# minimal_terminalv2_rc2014.net
KiCad netlist of a schematic drawn in EAGLE
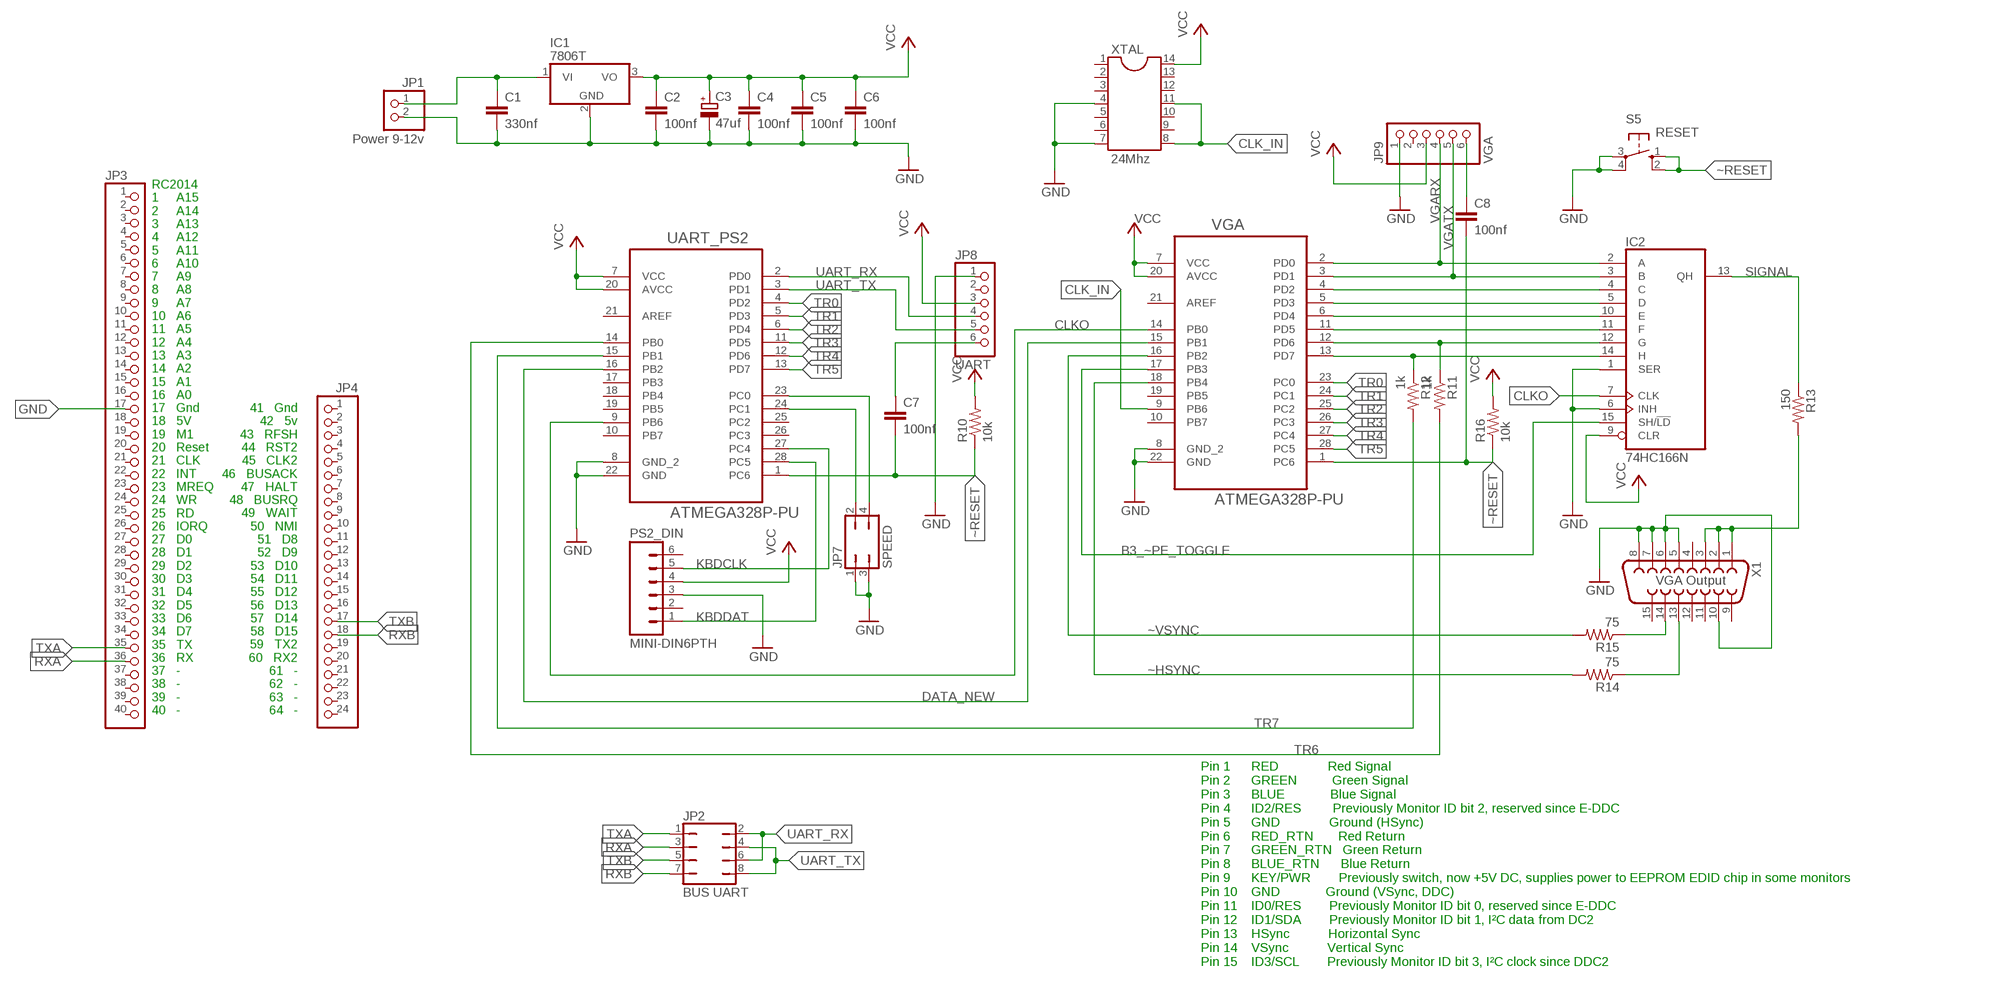
[diagram p0: schematic, sheet 1]

(export (version "E")
  (design (tool "Eeschema 10.0.6"))
  (components
    (comp (ref "C1")
      (value "330nf")
      (footprint "eagle-import:C2.5-3")
      (libsource (lib "eagle-import") (part "C2,5-3"))
    )
    (comp (ref "C2")
      (value "100nf")
      (footprint "eagle-import:C2.5-3")
      (libsource (lib "eagle-import") (part "C2,5-3"))
    )
    (comp (ref "C3")
      (value "47uf")
      (footprint "eagle-import:E2,5-6")
      (libsource (lib "eagle-import") (part "CPOL-EUE2.5-6"))
    )
    (comp (ref "C4")
      (value "100nf")
      (footprint "eagle-import:C2.5-3")
      (libsource (lib "eagle-import") (part "C2,5-3"))
    )
    (comp (ref "C5")
      (value "100nf")
      (footprint "eagle-import:C2.5-3")
      (libsource (lib "eagle-import") (part "C2,5-3"))
    )
    (comp (ref "C6")
      (value "100nf")
      (footprint "eagle-import:C2.5-3")
      (libsource (lib "eagle-import") (part "C2,5-3"))
    )
    (comp (ref "C7")
      (value "100nf")
      (footprint "eagle-import:C2.5-3")
      (libsource (lib "eagle-import") (part "C2,5-3"))
    )
    (comp (ref "C8")
      (value "100nf")
      (footprint "eagle-import:C2.5-3")
      (libsource (lib "eagle-import") (part "C2,5-3"))
    )
    (comp (ref "IC1")
      (value "7806T")
      (footprint "eagle-import:TO220H")
      (libsource (lib "eagle-import") (part "78T06"))
    )
    (comp (ref "IC2")
      (value "74HC166N")
      (footprint "eagle-import:DIL16")
      (libsource (lib "eagle-import") (part "74166NHC"))
    )
    (comp (ref "JP1")
      (value "Power 9-12v")
      (footprint "eagle-import:1X02")
      (libsource (lib "eagle-import") (part "PINHD-1X2"))
    )
    (comp (ref "JP2")
      (value "BUS UART")
      (footprint "eagle-import:JP4Q")
      (libsource (lib "eagle-import") (part "JP4Q"))
    )
    (comp (ref "JP3")
      (value "PINHD-1X40")
      (footprint "eagle-import:1X40")
      (libsource (lib "eagle-import") (part "PINHD-1X40"))
    )
    (comp (ref "JP4")
      (value "PINHD-1X24")
      (footprint "eagle-import:1X24")
      (libsource (lib "eagle-import") (part "PINHD-1X24"))
    )
    (comp (ref "JP7")
      (value "SPEED")
      (footprint "eagle-import:JP2Q")
      (libsource (lib "eagle-import") (part "JP2Q"))
    )
    (comp (ref "JP8")
      (value "UART")
      (footprint "eagle-import:1X06")
      (libsource (lib "eagle-import") (part "PINHD-1X6"))
    )
    (comp (ref "JP9")
      (value "VGA")
      (footprint "eagle-import:1X06")
      (libsource (lib "eagle-import") (part "PINHD-1X6"))
    )
    (comp (ref "PS2_DIN")
      (value "MINI-DIN6PTH")
      (footprint "eagle-import:MINI-DIN6")
      (libsource (lib "eagle-import") (part "MINI-DIN6PTH"))
    )
    (comp (ref "R10")
      (value "10k")
      (footprint "eagle-import:0204_7")
      (libsource (lib "eagle-import") (part "R-US_0204/7"))
    )
    (comp (ref "R11")
      (value "1k")
      (footprint "eagle-import:0204_7")
      (libsource (lib "eagle-import") (part "R-US_0204/7"))
    )
    (comp (ref "R12")
      (value "1k")
      (footprint "eagle-import:0204_7")
      (libsource (lib "eagle-import") (part "R-US_0204/7"))
    )
    (comp (ref "R13")
      (value "150")
      (footprint "eagle-import:0204_7")
      (libsource (lib "eagle-import") (part "R-US_0204/7"))
    )
    (comp (ref "R14")
      (value "75")
      (footprint "eagle-import:0204_7")
      (libsource (lib "eagle-import") (part "R-US_0204/7"))
    )
    (comp (ref "R15")
      (value "75")
      (footprint "eagle-import:0204_7")
      (libsource (lib "eagle-import") (part "R-US_0204/7"))
    )
    (comp (ref "R16")
      (value "10k")
      (footprint "eagle-import:0204_7")
      (libsource (lib "eagle-import") (part "R-US_0204/7"))
    )
    (comp (ref "S5")
      (value "RESET")
      (footprint "eagle-import:B3F-10XX")
      (fields (field (name "MPN") "B3F-1000"))
      (libsource (lib "eagle-import") (part "10-XX"))
    )
    (comp (ref "UART_PS2")
      (value "ATMEGA328P-PU")
      (footprint "eagle-import:DIP254P762X457-28")
      (libsource (lib "eagle-import") (part "ATMEGA328P-PU"))
    )
    (comp (ref "VGA")
      (value "ATMEGA328P-PU")
      (footprint "eagle-import:DIP254P762X457-28")
      (libsource (lib "eagle-import") (part "ATMEGA328P-PU"))
    )
    (comp (ref "X1")
      (value "VGA Output")
      (footprint "eagle-import:HDF15H")
      (libsource (lib "eagle-import") (part "F15HDH"))
    )
    (comp (ref "XTAL")
      (value "24Mhz")
      (footprint "eagle-import:SOCKET-14")
      (libsource (lib "eagle-import") (part "DIL14S"))
    )
  )
  (nets
    (net (code "1") (name "/B3_~{PE_TOGGLE}") (class "Default")
      (node (ref "IC2") (pin "15") (pinfunction "SH/~{LD}_15") (pintype "input"))
      (node (ref "VGA") (pin "17") (pinfunction "PB3_17") (pintype "bidirectional"))
    )
    (net (code "2") (name "/DATA_NEW") (class "Default")
      (node (ref "UART_PS2") (pin "16") (pinfunction "PB2_16") (pintype "bidirectional"))
      (node (ref "VGA") (pin "15") (pinfunction "PB1_15") (pintype "bidirectional"))
    )
    (net (code "3") (name "/KBDCLK") (class "Default")
      (node (ref "PS2_DIN") (pin "5") (pinfunction "5_5") (pintype "passive"))
      (node (ref "UART_PS2") (pin "27") (pinfunction "PC4_27") (pintype "bidirectional"))
    )
    (net (code "4") (name "/KBDDAT") (class "Default")
      (node (ref "PS2_DIN") (pin "1") (pinfunction "1_1") (pintype "passive"))
      (node (ref "UART_PS2") (pin "28") (pinfunction "PC5_28") (pintype "bidirectional"))
    )
    (net (code "5") (name "/SIGNAL") (class "Default")
      (node (ref "IC2") (pin "13") (pinfunction "QH_13") (pintype "output"))
      (node (ref "R13") (pin "1") (pinfunction "1_1") (pintype "passive"))
    )
    (net (code "6") (name "/TR6") (class "Default")
      (node (ref "R11") (pin "2") (pinfunction "2_2") (pintype "passive"))
      (node (ref "UART_PS2") (pin "14") (pinfunction "PB0_14") (pintype "bidirectional"))
    )
    (net (code "7") (name "/TR7") (class "Default")
      (node (ref "R12") (pin "2") (pinfunction "2_2") (pintype "passive"))
      (node (ref "UART_PS2") (pin "15") (pinfunction "PB1_15") (pintype "bidirectional"))
    )
    (net (code "8") (name "/VGARX") (class "Default")
      (node (ref "IC2") (pin "2") (pinfunction "A_2") (pintype "input"))
      (node (ref "JP9") (pin "4") (pinfunction "4_4") (pintype "passive"))
      (node (ref "VGA") (pin "2") (pinfunction "PD0_2") (pintype "bidirectional"))
    )
    (net (code "9") (name "/VGATX") (class "Default")
      (node (ref "IC2") (pin "3") (pinfunction "B_3") (pintype "input"))
      (node (ref "JP9") (pin "5") (pinfunction "5_5") (pintype "passive"))
      (node (ref "VGA") (pin "3") (pinfunction "PD1_3") (pintype "bidirectional"))
    )
    (net (code "10") (name "/~{HSYNC}") (class "Default")
      (node (ref "R14") (pin "2") (pinfunction "2_2") (pintype "passive"))
      (node (ref "VGA") (pin "18") (pinfunction "PB4_18") (pintype "bidirectional"))
    )
    (net (code "11") (name "/~{RESET}") (class "Default")
      (node (ref "C7") (pin "2") (pinfunction "2_2") (pintype "passive"))
      (node (ref "C8") (pin "2") (pinfunction "2_2") (pintype "passive"))
      (node (ref "R10") (pin "1") (pinfunction "1_1") (pintype "passive"))
      (node (ref "R16") (pin "1") (pinfunction "1_1") (pintype "passive"))
      (node (ref "S5") (pin "1") (pinfunction "S_1") (pintype "passive"))
      (node (ref "S5") (pin "2") (pinfunction "S1_2") (pintype "passive"))
      (node (ref "UART_PS2") (pin "1") (pinfunction "PC6_1") (pintype "bidirectional"))
      (node (ref "VGA") (pin "1") (pinfunction "PC6_1") (pintype "bidirectional"))
    )
    (net (code "12") (name "/~{VSYNC}") (class "Default")
      (node (ref "R15") (pin "2") (pinfunction "2_2") (pintype "passive"))
      (node (ref "VGA") (pin "16") (pinfunction "PB2_16") (pintype "bidirectional"))
    )
    (net (code "13") (name "CLKO") (class "Default")
      (node (ref "IC2") (pin "7") (pinfunction "CLK_7") (pintype "input"))
      (node (ref "UART_PS2") (pin "9") (pinfunction "PB6_9") (pintype "bidirectional"))
      (node (ref "VGA") (pin "14") (pinfunction "PB0_14") (pintype "bidirectional"))
    )
    (net (code "14") (name "CLK_IN") (class "Default")
      (node (ref "VGA") (pin "9") (pinfunction "PB6_9") (pintype "bidirectional"))
      (node (ref "XTAL") (pin "11") (pinfunction "11_11") (pintype "passive"))
      (node (ref "XTAL") (pin "8") (pinfunction "8_8") (pintype "passive"))
    )
    (net (code "15") (name "GND") (class "Default")
      (node (ref "C1") (pin "2") (pinfunction "2_2") (pintype "passive"))
      (node (ref "C2") (pin "2") (pinfunction "2_2") (pintype "passive"))
      (node (ref "C3") (pin "-") (pinfunction "-_-") (pintype "passive"))
      (node (ref "C4") (pin "2") (pinfunction "2_2") (pintype "passive"))
      (node (ref "C5") (pin "2") (pinfunction "2_2") (pintype "passive"))
      (node (ref "C6") (pin "2") (pinfunction "2_2") (pintype "passive"))
      (node (ref "IC1") (pin "2") (pinfunction "GND_2") (pintype "passive"))
      (node (ref "IC2") (pin "1") (pinfunction "SER_1") (pintype "input"))
      (node (ref "IC2") (pin "6") (pinfunction "INH_6") (pintype "input"))
      (node (ref "JP1") (pin "2") (pinfunction "2_2") (pintype "passive"))
      (node (ref "JP3") (pin "17") (pinfunction "17_17") (pintype "passive"))
      (node (ref "JP7") (pin "1") (pinfunction "1_1") (pintype "passive"))
      (node (ref "JP7") (pin "3") (pinfunction "3_3") (pintype "passive"))
      (node (ref "JP8") (pin "1") (pinfunction "1_1") (pintype "passive"))
      (node (ref "JP9") (pin "1") (pinfunction "1_1") (pintype "passive"))
      (node (ref "PS2_DIN") (pin "3") (pinfunction "3_3") (pintype "passive"))
      (node (ref "S5") (pin "3") (pinfunction "P_3") (pintype "passive"))
      (node (ref "S5") (pin "4") (pinfunction "P1_4") (pintype "passive"))
      (node (ref "UART_PS2") (pin "22") (pinfunction "GND_22") (pintype "passive"))
      (node (ref "UART_PS2") (pin "8") (pinfunction "GND_2_8") (pintype "passive"))
      (node (ref "VGA") (pin "22") (pinfunction "GND_22") (pintype "passive"))
      (node (ref "VGA") (pin "8") (pinfunction "GND_2_8") (pintype "passive"))
      (node (ref "X1") (pin "10") (pinfunction "10_10") (pintype "passive"))
      (node (ref "X1") (pin "5") (pinfunction "5_5") (pintype "passive"))
      (node (ref "X1") (pin "6") (pinfunction "6_6") (pintype "passive"))
      (node (ref "X1") (pin "7") (pinfunction "7_7") (pintype "passive"))
      (node (ref "X1") (pin "8") (pinfunction "8_8") (pintype "passive"))
      (node (ref "XTAL") (pin "4") (pinfunction "4_4") (pintype "passive"))
      (node (ref "XTAL") (pin "7") (pinfunction "7_7") (pintype "passive"))
    )
    (net (code "16") (name "Net-(C7-Pad1)") (class "Default")
      (node (ref "C7") (pin "1") (pinfunction "1_1") (pintype "passive"))
      (node (ref "JP8") (pin "6") (pinfunction "6_6") (pintype "passive"))
    )
    (net (code "17") (name "Net-(C8-Pad1)") (class "Default")
      (node (ref "C8") (pin "1") (pinfunction "1_1") (pintype "passive"))
      (node (ref "JP9") (pin "6") (pinfunction "6_6") (pintype "passive"))
    )
    (net (code "18") (name "Net-(IC1-VI)") (class "Default")
      (node (ref "C1") (pin "1") (pinfunction "1_1") (pintype "passive"))
      (node (ref "IC1") (pin "1") (pinfunction "VI_1") (pintype "input"))
      (node (ref "JP1") (pin "1") (pinfunction "1_1") (pintype "passive"))
    )
    (net (code "19") (name "Net-(IC2A-C)") (class "Default")
      (node (ref "IC2") (pin "4") (pinfunction "C_4") (pintype "input"))
      (node (ref "VGA") (pin "4") (pinfunction "PD2_4") (pintype "bidirectional"))
    )
    (net (code "20") (name "Net-(IC2A-D)") (class "Default")
      (node (ref "IC2") (pin "5") (pinfunction "D_5") (pintype "input"))
      (node (ref "VGA") (pin "5") (pinfunction "PD3_5") (pintype "bidirectional"))
    )
    (net (code "21") (name "Net-(IC2A-E)") (class "Default")
      (node (ref "IC2") (pin "10") (pinfunction "E_10") (pintype "input"))
      (node (ref "VGA") (pin "6") (pinfunction "PD4_6") (pintype "bidirectional"))
    )
    (net (code "22") (name "Net-(IC2A-F)") (class "Default")
      (node (ref "IC2") (pin "11") (pinfunction "F_11") (pintype "input"))
      (node (ref "VGA") (pin "11") (pinfunction "PD5_11") (pintype "bidirectional"))
    )
    (net (code "23") (name "Net-(IC2A-G)") (class "Default")
      (node (ref "IC2") (pin "12") (pinfunction "G_12") (pintype "input"))
      (node (ref "R11") (pin "1") (pinfunction "1_1") (pintype "passive"))
      (node (ref "VGA") (pin "12") (pinfunction "PD6_12") (pintype "bidirectional"))
    )
    (net (code "24") (name "Net-(IC2A-H)") (class "Default")
      (node (ref "IC2") (pin "14") (pinfunction "H_14") (pintype "input"))
      (node (ref "R12") (pin "1") (pinfunction "1_1") (pintype "passive"))
      (node (ref "VGA") (pin "13") (pinfunction "PD7_13") (pintype "bidirectional"))
    )
    (net (code "25") (name "Net-(R13-Pad2)") (class "Default")
      (node (ref "R13") (pin "2") (pinfunction "2_2") (pintype "passive"))
      (node (ref "X1") (pin "1") (pinfunction "1_1") (pintype "passive"))
      (node (ref "X1") (pin "2") (pinfunction "2_2") (pintype "passive"))
      (node (ref "X1") (pin "3") (pinfunction "3_3") (pintype "passive"))
    )
    (net (code "26") (name "Net-(R14-Pad1)") (class "Default")
      (node (ref "R14") (pin "1") (pinfunction "1_1") (pintype "passive"))
      (node (ref "X1") (pin "13") (pinfunction "13_13") (pintype "passive"))
    )
    (net (code "27") (name "Net-(R15-Pad1)") (class "Default")
      (node (ref "R15") (pin "1") (pinfunction "1_1") (pintype "passive"))
      (node (ref "X1") (pin "14") (pinfunction "14_14") (pintype "passive"))
    )
    (net (code "28") (name "Net-(UART_PS2-PC0)") (class "Default")
      (node (ref "JP7") (pin "4") (pinfunction "4_4") (pintype "passive"))
      (node (ref "UART_PS2") (pin "23") (pinfunction "PC0_23") (pintype "bidirectional"))
    )
    (net (code "29") (name "Net-(UART_PS2-PC1)") (class "Default")
      (node (ref "JP7") (pin "2") (pinfunction "2_2") (pintype "passive"))
      (node (ref "UART_PS2") (pin "24") (pinfunction "PC1_24") (pintype "bidirectional"))
    )
    (net (code "30") (name "RXA") (class "Default")
      (node (ref "JP2") (pin "3") (pinfunction "3_3") (pintype "passive"))
      (node (ref "JP3") (pin "36") (pinfunction "36_36") (pintype "passive"))
    )
    (net (code "31") (name "RXB") (class "Default")
      (node (ref "JP2") (pin "7") (pinfunction "7_7") (pintype "passive"))
      (node (ref "JP4") (pin "18") (pinfunction "18_18") (pintype "passive"))
    )
    (net (code "32") (name "TR0") (class "Default")
      (node (ref "UART_PS2") (pin "4") (pinfunction "PD2_4") (pintype "bidirectional"))
      (node (ref "VGA") (pin "23") (pinfunction "PC0_23") (pintype "bidirectional"))
    )
    (net (code "33") (name "TR1") (class "Default")
      (node (ref "UART_PS2") (pin "5") (pinfunction "PD3_5") (pintype "bidirectional"))
      (node (ref "VGA") (pin "24") (pinfunction "PC1_24") (pintype "bidirectional"))
    )
    (net (code "34") (name "TR2") (class "Default")
      (node (ref "UART_PS2") (pin "6") (pinfunction "PD4_6") (pintype "bidirectional"))
      (node (ref "VGA") (pin "25") (pinfunction "PC2_25") (pintype "bidirectional"))
    )
    (net (code "35") (name "TR3") (class "Default")
      (node (ref "UART_PS2") (pin "11") (pinfunction "PD5_11") (pintype "bidirectional"))
      (node (ref "VGA") (pin "26") (pinfunction "PC3_26") (pintype "bidirectional"))
    )
    (net (code "36") (name "TR4") (class "Default")
      (node (ref "UART_PS2") (pin "12") (pinfunction "PD6_12") (pintype "bidirectional"))
      (node (ref "VGA") (pin "27") (pinfunction "PC4_27") (pintype "bidirectional"))
    )
    (net (code "37") (name "TR5") (class "Default")
      (node (ref "UART_PS2") (pin "13") (pinfunction "PD7_13") (pintype "bidirectional"))
      (node (ref "VGA") (pin "28") (pinfunction "PC5_28") (pintype "bidirectional"))
    )
    (net (code "38") (name "TXA") (class "Default")
      (node (ref "JP2") (pin "1") (pinfunction "1_1") (pintype "passive"))
      (node (ref "JP3") (pin "35") (pinfunction "35_35") (pintype "passive"))
    )
    (net (code "39") (name "TXB") (class "Default")
      (node (ref "JP2") (pin "5") (pinfunction "5_5") (pintype "passive"))
      (node (ref "JP4") (pin "17") (pinfunction "17_17") (pintype "passive"))
    )
    (net (code "40") (name "UART_RX") (class "Default")
      (node (ref "JP2") (pin "2") (pinfunction "2_2") (pintype "passive"))
      (node (ref "JP2") (pin "6") (pinfunction "6_6") (pintype "passive"))
      (node (ref "JP8") (pin "4") (pinfunction "4_4") (pintype "passive"))
      (node (ref "UART_PS2") (pin "2") (pinfunction "PD0_2") (pintype "bidirectional"))
    )
    (net (code "41") (name "UART_TX") (class "Default")
      (node (ref "JP2") (pin "4") (pinfunction "4_4") (pintype "passive"))
      (node (ref "JP2") (pin "8") (pinfunction "8_8") (pintype "passive"))
      (node (ref "JP8") (pin "5") (pinfunction "5_5") (pintype "passive"))
      (node (ref "UART_PS2") (pin "3") (pinfunction "PD1_3") (pintype "bidirectional"))
    )
    (net (code "42") (name "VCC") (class "Default")
      (node (ref "C2") (pin "1") (pinfunction "1_1") (pintype "passive"))
      (node (ref "C3") (pin "+") (pinfunction "+_+") (pintype "passive"))
      (node (ref "C4") (pin "1") (pinfunction "1_1") (pintype "passive"))
      (node (ref "C5") (pin "1") (pinfunction "1_1") (pintype "passive"))
      (node (ref "C6") (pin "1") (pinfunction "1_1") (pintype "passive"))
      (node (ref "IC1") (pin "3") (pinfunction "VO_3") (pintype "passive"))
      (node (ref "IC2") (pin "9") (pinfunction "CLR_9") (pintype "input"))
      (node (ref "JP8") (pin "3") (pinfunction "3_3") (pintype "passive"))
      (node (ref "JP9") (pin "3") (pinfunction "3_3") (pintype "passive"))
      (node (ref "PS2_DIN") (pin "4") (pinfunction "4_4") (pintype "passive"))
      (node (ref "R10") (pin "2") (pinfunction "2_2") (pintype "passive"))
      (node (ref "R16") (pin "2") (pinfunction "2_2") (pintype "passive"))
      (node (ref "UART_PS2") (pin "20") (pinfunction "AVCC_20") (pintype "power_in"))
      (node (ref "UART_PS2") (pin "7") (pinfunction "VCC_7") (pintype "power_in"))
      (node (ref "VGA") (pin "20") (pinfunction "AVCC_20") (pintype "power_in"))
      (node (ref "VGA") (pin "7") (pinfunction "VCC_7") (pintype "power_in"))
      (node (ref "XTAL") (pin "14") (pinfunction "14_14") (pintype "passive"))
    )
    (net (code "43") (name "unconnected-(JP3-Pad1)") (class "Default")
      (node (ref "JP3") (pin "1") (pinfunction "1_1") (pintype "passive"))
    )
    (net (code "44") (name "unconnected-(JP3-Pad2)") (class "Default")
      (node (ref "JP3") (pin "2") (pinfunction "2_2") (pintype "passive"))
    )
    (net (code "45") (name "unconnected-(JP3-Pad3)") (class "Default")
      (node (ref "JP3") (pin "3") (pinfunction "3_3") (pintype "passive"))
    )
    (net (code "46") (name "unconnected-(JP3-Pad4)") (class "Default")
      (node (ref "JP3") (pin "4") (pinfunction "4_4") (pintype "passive"))
    )
    (net (code "47") (name "unconnected-(JP3-Pad5)") (class "Default")
      (node (ref "JP3") (pin "5") (pinfunction "5_5") (pintype "passive"))
    )
    (net (code "48") (name "unconnected-(JP3-Pad6)") (class "Default")
      (node (ref "JP3") (pin "6") (pinfunction "6_6") (pintype "passive"))
    )
    (net (code "49") (name "unconnected-(JP3-Pad7)") (class "Default")
      (node (ref "JP3") (pin "7") (pinfunction "7_7") (pintype "passive"))
    )
    (net (code "50") (name "unconnected-(JP3-Pad8)") (class "Default")
      (node (ref "JP3") (pin "8") (pinfunction "8_8") (pintype "passive"))
    )
    (net (code "51") (name "unconnected-(JP3-Pad9)") (class "Default")
      (node (ref "JP3") (pin "9") (pinfunction "9_9") (pintype "passive"))
    )
    (net (code "52") (name "unconnected-(JP3-Pad10)") (class "Default")
      (node (ref "JP3") (pin "10") (pinfunction "10_10") (pintype "passive"))
    )
    (net (code "53") (name "unconnected-(JP3-Pad11)") (class "Default")
      (node (ref "JP3") (pin "11") (pinfunction "11_11") (pintype "passive"))
    )
    (net (code "54") (name "unconnected-(JP3-Pad12)") (class "Default")
      (node (ref "JP3") (pin "12") (pinfunction "12_12") (pintype "passive"))
    )
    (net (code "55") (name "unconnected-(JP3-Pad13)") (class "Default")
      (node (ref "JP3") (pin "13") (pinfunction "13_13") (pintype "passive"))
    )
    (net (code "56") (name "unconnected-(JP3-Pad14)") (class "Default")
      (node (ref "JP3") (pin "14") (pinfunction "14_14") (pintype "passive"))
    )
    (net (code "57") (name "unconnected-(JP3-Pad15)") (class "Default")
      (node (ref "JP3") (pin "15") (pinfunction "15_15") (pintype "passive"))
    )
    (net (code "58") (name "unconnected-(JP3-Pad16)") (class "Default")
      (node (ref "JP3") (pin "16") (pinfunction "16_16") (pintype "passive"))
    )
    (net (code "59") (name "unconnected-(JP3-Pad18)") (class "Default")
      (node (ref "JP3") (pin "18") (pinfunction "18_18") (pintype "passive"))
    )
    (net (code "60") (name "unconnected-(JP3-Pad19)") (class "Default")
      (node (ref "JP3") (pin "19") (pinfunction "19_19") (pintype "passive"))
    )
    (net (code "61") (name "unconnected-(JP3-Pad20)") (class "Default")
      (node (ref "JP3") (pin "20") (pinfunction "20_20") (pintype "passive"))
    )
    (net (code "62") (name "unconnected-(JP3-Pad21)") (class "Default")
      (node (ref "JP3") (pin "21") (pinfunction "21_21") (pintype "passive"))
    )
    (net (code "63") (name "unconnected-(JP3-Pad22)") (class "Default")
      (node (ref "JP3") (pin "22") (pinfunction "22_22") (pintype "passive"))
    )
    (net (code "64") (name "unconnected-(JP3-Pad23)") (class "Default")
      (node (ref "JP3") (pin "23") (pinfunction "23_23") (pintype "passive"))
    )
    (net (code "65") (name "unconnected-(JP3-Pad24)") (class "Default")
      (node (ref "JP3") (pin "24") (pinfunction "24_24") (pintype "passive"))
    )
    (net (code "66") (name "unconnected-(JP3-Pad25)") (class "Default")
      (node (ref "JP3") (pin "25") (pinfunction "25_25") (pintype "passive"))
    )
    (net (code "67") (name "unconnected-(JP3-Pad26)") (class "Default")
      (node (ref "JP3") (pin "26") (pinfunction "26_26") (pintype "passive"))
    )
    (net (code "68") (name "unconnected-(JP3-Pad27)") (class "Default")
      (node (ref "JP3") (pin "27") (pinfunction "27_27") (pintype "passive"))
    )
    (net (code "69") (name "unconnected-(JP3-Pad28)") (class "Default")
      (node (ref "JP3") (pin "28") (pinfunction "28_28") (pintype "passive"))
    )
    (net (code "70") (name "unconnected-(JP3-Pad29)") (class "Default")
      (node (ref "JP3") (pin "29") (pinfunction "29_29") (pintype "passive"))
    )
    (net (code "71") (name "unconnected-(JP3-Pad30)") (class "Default")
      (node (ref "JP3") (pin "30") (pinfunction "30_30") (pintype "passive"))
    )
    (net (code "72") (name "unconnected-(JP3-Pad31)") (class "Default")
      (node (ref "JP3") (pin "31") (pinfunction "31_31") (pintype "passive"))
    )
    (net (code "73") (name "unconnected-(JP3-Pad32)") (class "Default")
      (node (ref "JP3") (pin "32") (pinfunction "32_32") (pintype "passive"))
    )
    (net (code "74") (name "unconnected-(JP3-Pad33)") (class "Default")
      (node (ref "JP3") (pin "33") (pinfunction "33_33") (pintype "passive"))
    )
    (net (code "75") (name "unconnected-(JP3-Pad34)") (class "Default")
      (node (ref "JP3") (pin "34") (pinfunction "34_34") (pintype "passive"))
    )
    (net (code "76") (name "unconnected-(JP3-Pad37)") (class "Default")
      (node (ref "JP3") (pin "37") (pinfunction "37_37") (pintype "passive"))
    )
    (net (code "77") (name "unconnected-(JP3-Pad38)") (class "Default")
      (node (ref "JP3") (pin "38") (pinfunction "38_38") (pintype "passive"))
    )
    (net (code "78") (name "unconnected-(JP3-Pad39)") (class "Default")
      (node (ref "JP3") (pin "39") (pinfunction "39_39") (pintype "passive"))
    )
    (net (code "79") (name "unconnected-(JP3-Pad40)") (class "Default")
      (node (ref "JP3") (pin "40") (pinfunction "40_40") (pintype "passive"))
    )
    (net (code "80") (name "unconnected-(JP4-Pad1)") (class "Default")
      (node (ref "JP4") (pin "1") (pinfunction "1_1") (pintype "passive"))
    )
    (net (code "81") (name "unconnected-(JP4-Pad2)") (class "Default")
      (node (ref "JP4") (pin "2") (pinfunction "2_2") (pintype "passive"))
    )
    (net (code "82") (name "unconnected-(JP4-Pad3)") (class "Default")
      (node (ref "JP4") (pin "3") (pinfunction "3_3") (pintype "passive"))
    )
    (net (code "83") (name "unconnected-(JP4-Pad4)") (class "Default")
      (node (ref "JP4") (pin "4") (pinfunction "4_4") (pintype "passive"))
    )
    (net (code "84") (name "unconnected-(JP4-Pad5)") (class "Default")
      (node (ref "JP4") (pin "5") (pinfunction "5_5") (pintype "passive"))
    )
    (net (code "85") (name "unconnected-(JP4-Pad6)") (class "Default")
      (node (ref "JP4") (pin "6") (pinfunction "6_6") (pintype "passive"))
    )
    (net (code "86") (name "unconnected-(JP4-Pad7)") (class "Default")
      (node (ref "JP4") (pin "7") (pinfunction "7_7") (pintype "passive"))
    )
    (net (code "87") (name "unconnected-(JP4-Pad8)") (class "Default")
      (node (ref "JP4") (pin "8") (pinfunction "8_8") (pintype "passive"))
    )
    (net (code "88") (name "unconnected-(JP4-Pad9)") (class "Default")
      (node (ref "JP4") (pin "9") (pinfunction "9_9") (pintype "passive"))
    )
    (net (code "89") (name "unconnected-(JP4-Pad10)") (class "Default")
      (node (ref "JP4") (pin "10") (pinfunction "10_10") (pintype "passive"))
    )
    (net (code "90") (name "unconnected-(JP4-Pad11)") (class "Default")
      (node (ref "JP4") (pin "11") (pinfunction "11_11") (pintype "passive"))
    )
    (net (code "91") (name "unconnected-(JP4-Pad12)") (class "Default")
      (node (ref "JP4") (pin "12") (pinfunction "12_12") (pintype "passive"))
    )
    (net (code "92") (name "unconnected-(JP4-Pad13)") (class "Default")
      (node (ref "JP4") (pin "13") (pinfunction "13_13") (pintype "passive"))
    )
    (net (code "93") (name "unconnected-(JP4-Pad14)") (class "Default")
      (node (ref "JP4") (pin "14") (pinfunction "14_14") (pintype "passive"))
    )
    (net (code "94") (name "unconnected-(JP4-Pad15)") (class "Default")
      (node (ref "JP4") (pin "15") (pinfunction "15_15") (pintype "passive"))
    )
    (net (code "95") (name "unconnected-(JP4-Pad16)") (class "Default")
      (node (ref "JP4") (pin "16") (pinfunction "16_16") (pintype "passive"))
    )
    (net (code "96") (name "unconnected-(JP4-Pad19)") (class "Default")
      (node (ref "JP4") (pin "19") (pinfunction "19_19") (pintype "passive"))
    )
    (net (code "97") (name "unconnected-(JP4-Pad20)") (class "Default")
      (node (ref "JP4") (pin "20") (pinfunction "20_20") (pintype "passive"))
    )
    (net (code "98") (name "unconnected-(JP4-Pad21)") (class "Default")
      (node (ref "JP4") (pin "21") (pinfunction "21_21") (pintype "passive"))
    )
    (net (code "99") (name "unconnected-(JP4-Pad22)") (class "Default")
      (node (ref "JP4") (pin "22") (pinfunction "22_22") (pintype "passive"))
    )
    (net (code "100") (name "unconnected-(JP4-Pad23)") (class "Default")
      (node (ref "JP4") (pin "23") (pinfunction "23_23") (pintype "passive"))
    )
    (net (code "101") (name "unconnected-(JP4-Pad24)") (class "Default")
      (node (ref "JP4") (pin "24") (pinfunction "24_24") (pintype "passive"))
    )
    (net (code "102") (name "unconnected-(JP8-Pad2)") (class "Default")
      (node (ref "JP8") (pin "2") (pinfunction "2_2") (pintype "passive"))
    )
    (net (code "103") (name "unconnected-(JP9-Pad2)") (class "Default")
      (node (ref "JP9") (pin "2") (pinfunction "2_2") (pintype "passive"))
    )
    (net (code "104") (name "unconnected-(PS2_DIN-Pad2)") (class "Default")
      (node (ref "PS2_DIN") (pin "2") (pinfunction "2_2") (pintype "passive"))
    )
    (net (code "105") (name "unconnected-(PS2_DIN-Pad6)") (class "Default")
      (node (ref "PS2_DIN") (pin "6") (pinfunction "6_6") (pintype "passive"))
    )
    (net (code "106") (name "unconnected-(UART_PS2-AREF-Pad21)") (class "Default")
      (node (ref "UART_PS2") (pin "21") (pinfunction "AREF_21") (pintype "input"))
    )
    (net (code "107") (name "unconnected-(UART_PS2-PB3-Pad17)") (class "Default")
      (node (ref "UART_PS2") (pin "17") (pinfunction "PB3_17") (pintype "bidirectional"))
    )
    (net (code "108") (name "unconnected-(UART_PS2-PB4-Pad18)") (class "Default")
      (node (ref "UART_PS2") (pin "18") (pinfunction "PB4_18") (pintype "bidirectional"))
    )
    (net (code "109") (name "unconnected-(UART_PS2-PB5-Pad19)") (class "Default")
      (node (ref "UART_PS2") (pin "19") (pinfunction "PB5_19") (pintype "bidirectional"))
    )
    (net (code "110") (name "unconnected-(UART_PS2-PB7-Pad10)") (class "Default")
      (node (ref "UART_PS2") (pin "10") (pinfunction "PB7_10") (pintype "bidirectional"))
    )
    (net (code "111") (name "unconnected-(UART_PS2-PC2-Pad25)") (class "Default")
      (node (ref "UART_PS2") (pin "25") (pinfunction "PC2_25") (pintype "bidirectional"))
    )
    (net (code "112") (name "unconnected-(UART_PS2-PC3-Pad26)") (class "Default")
      (node (ref "UART_PS2") (pin "26") (pinfunction "PC3_26") (pintype "bidirectional"))
    )
    (net (code "113") (name "unconnected-(VGA-AREF-Pad21)") (class "Default")
      (node (ref "VGA") (pin "21") (pinfunction "AREF_21") (pintype "input"))
    )
    (net (code "114") (name "unconnected-(VGA-PB5-Pad19)") (class "Default")
      (node (ref "VGA") (pin "19") (pinfunction "PB5_19") (pintype "bidirectional"))
    )
    (net (code "115") (name "unconnected-(VGA-PB7-Pad10)") (class "Default")
      (node (ref "VGA") (pin "10") (pinfunction "PB7_10") (pintype "bidirectional"))
    )
    (net (code "116") (name "unconnected-(X1-Pad4)") (class "Default")
      (node (ref "X1") (pin "4") (pinfunction "4_4") (pintype "passive"))
    )
    (net (code "117") (name "unconnected-(X1-Pad9)") (class "Default")
      (node (ref "X1") (pin "9") (pinfunction "9_9") (pintype "passive"))
    )
    (net (code "118") (name "unconnected-(X1-Pad11)") (class "Default")
      (node (ref "X1") (pin "11") (pinfunction "11_11") (pintype "passive"))
    )
    (net (code "119") (name "unconnected-(X1-Pad12)") (class "Default")
      (node (ref "X1") (pin "12") (pinfunction "12_12") (pintype "passive"))
    )
    (net (code "120") (name "unconnected-(X1-Pad15)") (class "Default")
      (node (ref "X1") (pin "15") (pinfunction "15_15") (pintype "passive"))
    )
    (net (code "121") (name "unconnected-(XTAL-Pad1)") (class "Default")
      (node (ref "XTAL") (pin "1") (pinfunction "1_1") (pintype "passive"))
    )
    (net (code "122") (name "unconnected-(XTAL-Pad2)") (class "Default")
      (node (ref "XTAL") (pin "2") (pinfunction "2_2") (pintype "passive"))
    )
    (net (code "123") (name "unconnected-(XTAL-Pad3)") (class "Default")
      (node (ref "XTAL") (pin "3") (pinfunction "3_3") (pintype "passive"))
    )
    (net (code "124") (name "unconnected-(XTAL-Pad5)") (class "Default")
      (node (ref "XTAL") (pin "5") (pinfunction "5_5") (pintype "passive"))
    )
    (net (code "125") (name "unconnected-(XTAL-Pad6)") (class "Default")
      (node (ref "XTAL") (pin "6") (pinfunction "6_6") (pintype "passive"))
    )
    (net (code "126") (name "unconnected-(XTAL-Pad9)") (class "Default")
      (node (ref "XTAL") (pin "9") (pinfunction "9_9") (pintype "passive"))
    )
    (net (code "127") (name "unconnected-(XTAL-Pad10)") (class "Default")
      (node (ref "XTAL") (pin "10") (pinfunction "10_10") (pintype "passive"))
    )
    (net (code "128") (name "unconnected-(XTAL-Pad12)") (class "Default")
      (node (ref "XTAL") (pin "12") (pinfunction "12_12") (pintype "passive"))
    )
    (net (code "129") (name "unconnected-(XTAL-Pad13)") (class "Default")
      (node (ref "XTAL") (pin "13") (pinfunction "13_13") (pintype "passive"))
    )
  )
)
